# test.net
KiCad netlist of a schematic drawn in Altium Designer
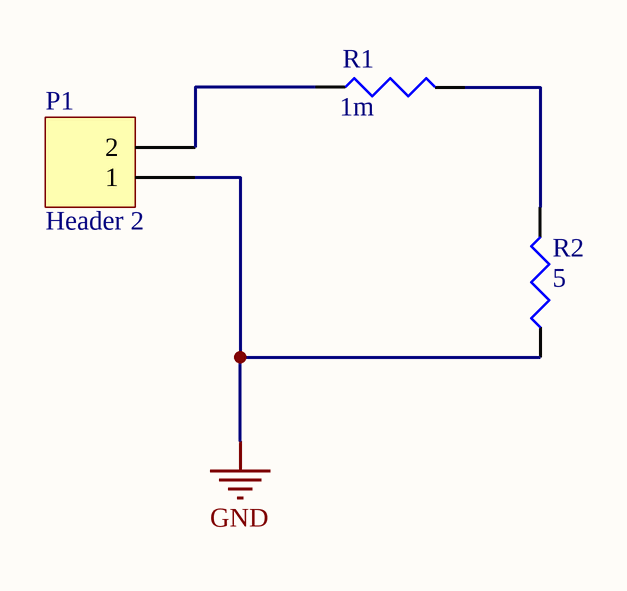
[diagram p0: test.SchDoc]

(export (version "E")
  (design (tool "Eeschema 10.0.6"))
  (components
    (comp (ref "P1")
      (value "Header 2")
      (footprint "HDR1X2")
      (description "Header, 2-Pin")
      (fields (field (name "PUBLISHER") "Altium Limited"))
      (libsource (lib "Miscellaneous Connectors") (part "Header 2"))
    )
    (comp (ref "R1")
      (value "1m")
      (footprint "J1-0603")
      (description "Resistor")
      (fields (field (name "PUBLISHER") "Altium Limited"))
      (libsource (lib "Miscellaneous Devices") (part "Res3"))
    )
    (comp (ref "R2")
      (value "5")
      (footprint "J1-0603")
      (description "Resistor")
      (fields (field (name "PUBLISHER") "Altium Limited"))
      (libsource (lib "Miscellaneous Devices") (part "Res3"))
    )
  )
  (nets
    (net (code "1") (name "GND") (class "Default")
      (node (ref "P1") (pin "1") (pinfunction "1_1") (pintype "passive"))
      (node (ref "R2") (pin "1") (pinfunction "1_1") (pintype "passive"))
    )
    (net (code "2") (name "Net-(P1-Pad2)") (class "Default")
      (node (ref "P1") (pin "2") (pinfunction "2_2") (pintype "passive"))
      (node (ref "R1") (pin "1") (pinfunction "1_1") (pintype "passive"))
    )
    (net (code "3") (name "Net-(R1-Pad2)") (class "Default")
      (node (ref "R1") (pin "2") (pinfunction "2_2") (pintype "passive"))
      (node (ref "R2") (pin "2") (pinfunction "2_2") (pintype "passive"))
    )
  )
)
